# REACTION-CIRCUIT-CONTROL.net
KiCad netlist of a schematic drawn in Altium Designer
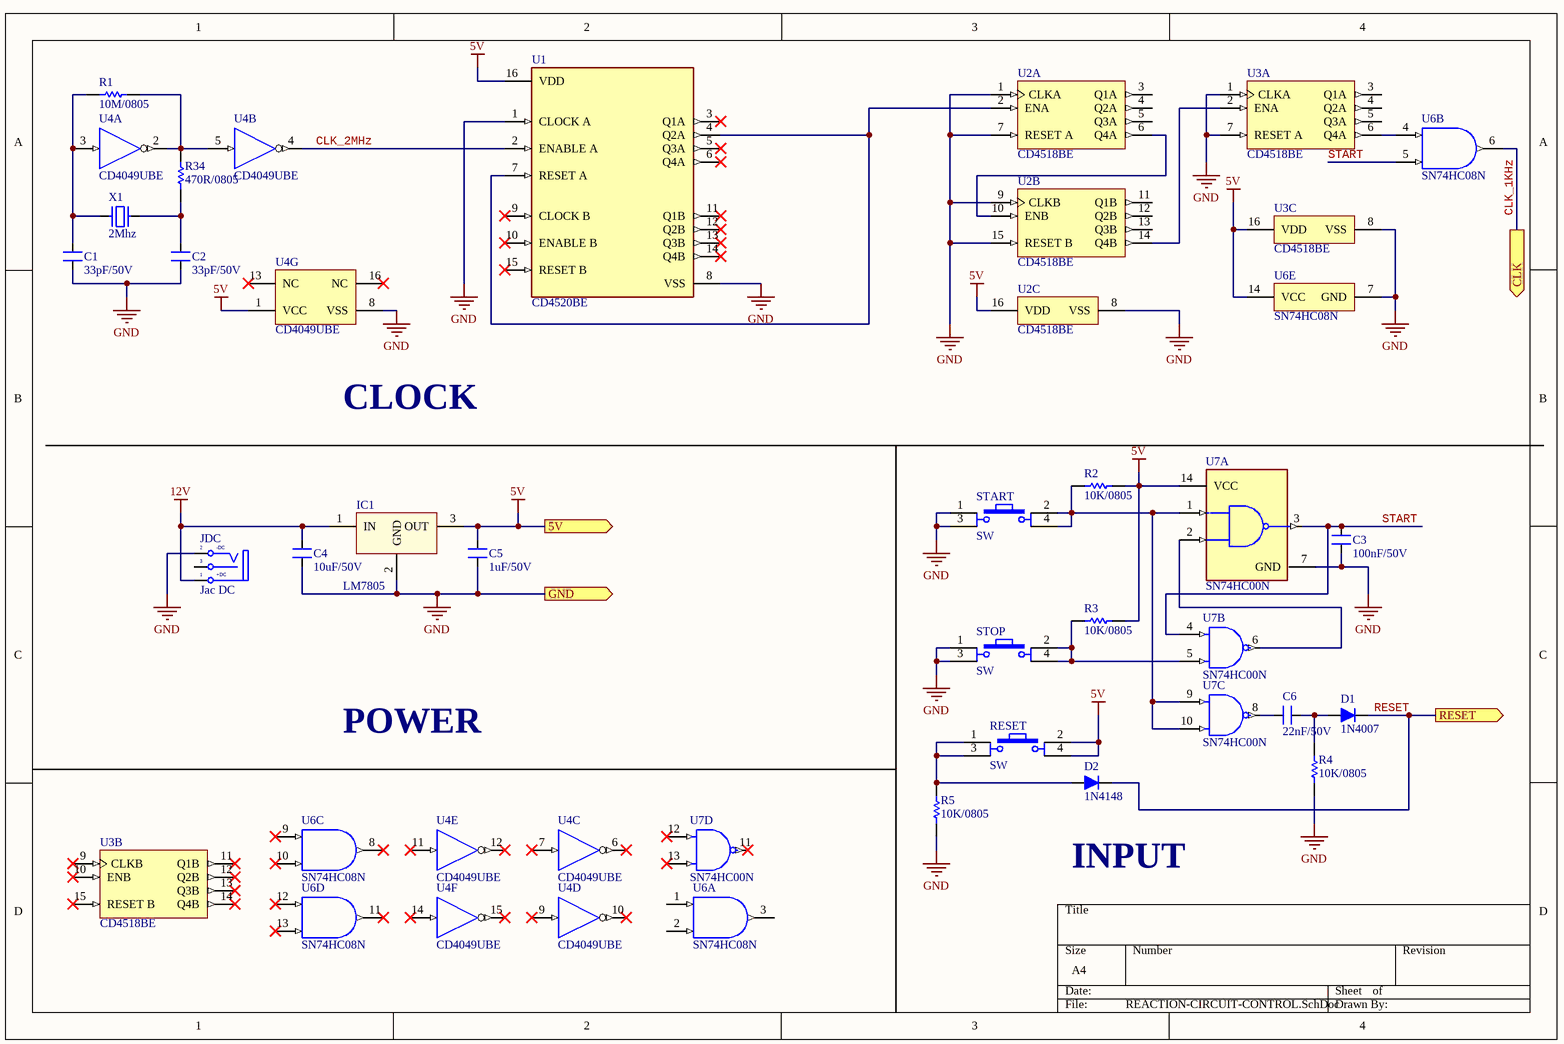
[diagram p0: REACTION-CIRCUIT-CONTROL.SchDoc]

(export (version "E")
  (design (tool "Eeschema 10.0.6"))
  (components
    (comp (ref "C1")
      (value "33pF/50V")
      (footprint "Cap 0805(2012)")
      (description "Ceramic Capacitor 1nF/50V (+-20% TH)/(+10%SMD)")
      (libsource (lib "Duc") (part "CAP_CER_1nF_50V_NPOL"))
    )
    (comp (ref "C2")
      (value "33pF/50V")
      (footprint "Cap 0805(2012)")
      (description "Ceramic Capacitor 1nF/50V (+-20% TH)/(+10%SMD)")
      (libsource (lib "Duc") (part "CAP_CER_1nF_50V_NPOL"))
    )
    (comp (ref "C3")
      (value "100nF/50V")
      (footprint "Cap 0805(2012)")
      (description "Ceramic Capacitor 1nF/50V (+-20% TH)/(+10%SMD)")
      (libsource (lib "Duc") (part "CAP_CER_1nF_50V_NPOL"))
    )
    (comp (ref "C4")
      (value "10uF/50V")
      (footprint "Cap 0805(2012)")
      (description "Ceramic Capacitor 1nF/50V (+-20% TH)/(+10%SMD)")
      (libsource (lib "Duc") (part "CAP_CER_1nF_50V_NPOL"))
    )
    (comp (ref "C5")
      (value "1uF/50V")
      (footprint "Cap 0805(2012)")
      (description "Ceramic Capacitor 1nF/50V (+-20% TH)/(+10%SMD)")
      (libsource (lib "Duc") (part "CAP_CER_1nF_50V_NPOL"))
    )
    (comp (ref "C6")
      (value "22nF/50V")
      (footprint "Cap 0805(2012)")
      (description "Ceramic Capacitor 1nF/50V (+-20% TH)/(+10%SMD)")
      (libsource (lib "Duc") (part "CAP_CER_1nF_50V_NPOL"))
    )
    (comp (ref "D1")
      (value "1N4007")
      (footprint "1N4007")
      (description "Diode LS 1A 1000V DO-41")
      (libsource (lib "Duc") (part "1N4007"))
    )
    (comp (ref "D2")
      (value "1N4148")
      (footprint "1N4007")
      (description "Diode LS 1A 1000V DO-41")
      (libsource (lib "Duc") (part "1N4007"))
    )
    (comp (ref "IC1")
      (value "LM7805")
      (footprint "QTO-220H3")
      (description "On ap +, from + 5 to + 24VDC")
      (libsource (lib "MinhHa_Integrated_Library") (part "LM78xx"))
    )
    (comp (ref "JDC")
      (value "Jac DC")
      (footprint "DC-IN")
      (description "Jac DC input")
      (libsource (lib "MinhHa_Integrated_Library") (part "DCIN"))
    )
    (comp (ref "R1")
      (value "10M/0805")
      (footprint "Res 0805(2012)")
      (description "Resistor 0805")
      (libsource (lib "Duc") (part "Resistor 0805"))
    )
    (comp (ref "R2")
      (value "10K/0805")
      (footprint "Res 0805(2012)")
      (description "Resistor 0805")
      (libsource (lib "Duc") (part "Resistor 0805"))
    )
    (comp (ref "R3")
      (value "10K/0805")
      (footprint "Res 0805(2012)")
      (description "Resistor 0805")
      (libsource (lib "Duc") (part "Resistor 0805"))
    )
    (comp (ref "R4")
      (value "10K/0805")
      (footprint "Res 0805(2012)")
      (description "Resistor 0805")
      (libsource (lib "Duc") (part "Resistor 0805"))
    )
    (comp (ref "R5")
      (value "10K/0805")
      (footprint "Res 0805(2012)")
      (description "Resistor 0805")
      (libsource (lib "Duc") (part "Resistor 0805"))
    )
    (comp (ref "R34")
      (value "470R/0805")
      (footprint "Res 0805(2012)")
      (description "Resistor 0805")
      (libsource (lib "Duc") (part "Resistor 0805"))
    )
    (comp (ref "RESET")
      (value "SW")
      (footprint "SW4B")
      (description "Switch button 4 pin")
      (libsource (lib "MinhHa_Integrated_Library") (part "SW4"))
    )
    (comp (ref "START")
      (value "SW")
      (footprint "SW4B")
      (description "Switch button 4 pin")
      (libsource (lib "MinhHa_Integrated_Library") (part "SW4"))
    )
    (comp (ref "STOP")
      (value "SW")
      (footprint "SW4B")
      (description "Switch button 4 pin")
      (libsource (lib "MinhHa_Integrated_Library") (part "SW4"))
    )
    (comp (ref "U1")
      (value "CD4520BE")
      (footprint "FP-N0016A-MFG")
      (description "IC DUAL BINARY UP COUNTER 16-DIP")
      (libsource (lib "Altium Content Vault") (part "bdd40e6c57bfb003857edd1337e34ab"))
    )
    (comp (ref "U2")
      (value "CD4518BE")
      (footprint "N0016A")
      (description "CMOS Dual BCD Up-Counter, N0016A, TUBE")
      (fields
        (field (name "MANUFACTURER") "Texas Instruments")
        (field (name "GENERIC PART NUMBER") "CD4518B")
      )
      (libsource (lib "Altium Content Vault") (part "TI-CD45XXB-16"))
    )
    (comp (ref "U3")
      (value "CD4518BE")
      (footprint "N0016A")
      (description "CMOS Dual BCD Up-Counter, N0016A, TUBE")
      (fields
        (field (name "MANUFACTURER") "Texas Instruments")
        (field (name "GENERIC PART NUMBER") "CD4518B")
      )
      (libsource (lib "Altium Content Vault") (part "TI-CD45XXB-16"))
    )
    (comp (ref "U4")
      (value "CD4049UBE")
      (footprint "N0016A")
      (description "CMOS Hex Inverting Buffer/Converter, N0016A, TUBE")
      (fields
        (field (name "GENERIC PART NUMBER") "CD4049UB")
        (field (name "MANUFACTURER") "Texas Instruments")
      )
      (libsource (lib "Altium Content Vault") (part "TI-CD4049UB-16"))
    )
    (comp (ref "U6")
      (value "SN74HC08N")
      (footprint "N0014A")
      (description "Quadruple 2-Input Positive-AND Gates, N0014A, TUBE")
      (fields
        (field (name "GENERIC PART NUMBER") "SN74HC08")
        (field (name "MANUFACTURER") "Texas Instruments")
      )
      (libsource (lib "Altium Content Vault") (part "TI-AND-4-2IN-14"))
    )
    (comp (ref "U7")
      (value "SN74HC00N")
      (footprint "FP-N0014A-MFG")
      (description "IC GATE NAND 4CH 2-INP 14DIP")
      (libsource (lib "Altium Content Vault") (part "0b9c136352749c62e1c326cbc0064d4"))
    )
    (comp (ref "X1")
      (value "2Mhz")
      (footprint "XT2")
      (description "Crystal, 32.768 KHz, -40 to 85 degC, 3.2 x 1.5 x 0.9 mm SMD")
      (libsource (lib "LIBRARY_MuaLinhKien") (part "XT2"))
    )
  )
  (nets
    (net (code "1") (name "/CLK_1KHz") (class "Default")
      (node (ref "U6") (pin "6") (pinfunction "2Y_6") (pintype "output"))
    )
    (net (code "2") (name "/CLK_2MHz") (class "Default")
      (node (ref "U1") (pin "2") (pinfunction "ENABLE_A_2") (pintype "input"))
      (node (ref "U4") (pin "4") (pinfunction "H=~{B}_4") (pintype "output"))
    )
    (net (code "3") (name "/RESET") (class "Default")
      (node (ref "D1") (pin "2") (pinfunction "K_2") (pintype "passive"))
      (node (ref "D2") (pin "2") (pinfunction "K_2") (pintype "passive"))
    )
    (net (code "4") (name "/START") (class "Default")
      (node (ref "C3") (pin "2") (pinfunction "2_2") (pintype "passive"))
      (node (ref "U6") (pin "5") (pinfunction "2B_5") (pintype "input"))
      (node (ref "U7") (pin "3") (pinfunction "1Y_3") (pintype "output"))
      (node (ref "U7") (pin "4") (pinfunction "2A_4") (pintype "input"))
    )
    (net (code "5") (name "5V") (class "Default")
      (node (ref "C5") (pin "2") (pinfunction "2_2") (pintype "passive"))
      (node (ref "IC1") (pin "3") (pinfunction "OUT_3") (pintype "passive"))
      (node (ref "R2") (pin "2") (pinfunction "2_2") (pintype "passive"))
      (node (ref "R3") (pin "2") (pinfunction "2_2") (pintype "passive"))
      (node (ref "RESET") (pin "2") (pintype "passive"))
      (node (ref "RESET") (pin "4") (pintype "passive"))
      (node (ref "U1") (pin "16") (pinfunction "VDD_16") (pintype "power_in"))
      (node (ref "U2") (pin "16") (pinfunction "VDD_16") (pintype "power_in"))
      (node (ref "U3") (pin "16") (pinfunction "VDD_16") (pintype "power_in"))
      (node (ref "U4") (pin "1") (pinfunction "VCC_1") (pintype "power_in"))
      (node (ref "U6") (pin "14") (pinfunction "VCC_14") (pintype "power_in"))
      (node (ref "U7") (pin "14") (pinfunction "VCC_14") (pintype "power_in"))
    )
    (net (code "6") (name "12V") (class "Default")
      (node (ref "C4") (pin "2") (pinfunction "2_2") (pintype "passive"))
      (node (ref "IC1") (pin "1") (pinfunction "IN_1") (pintype "passive"))
      (node (ref "JDC") (pin "1") (pinfunction "T_1") (pintype "passive"))
    )
    (net (code "7") (name "GND") (class "Default")
      (node (ref "C1") (pin "1") (pinfunction "1_1") (pintype "passive"))
      (node (ref "C2") (pin "1") (pinfunction "1_1") (pintype "passive"))
      (node (ref "C3") (pin "1") (pinfunction "1_1") (pintype "passive"))
      (node (ref "C4") (pin "1") (pinfunction "1_1") (pintype "passive"))
      (node (ref "C5") (pin "1") (pinfunction "1_1") (pintype "passive"))
      (node (ref "IC1") (pin "2") (pinfunction "GND_2") (pintype "passive"))
      (node (ref "JDC") (pin "2") (pinfunction "TN_2") (pintype "passive"))
      (node (ref "R4") (pin "2") (pinfunction "2_2") (pintype "passive"))
      (node (ref "R5") (pin "2") (pinfunction "2_2") (pintype "passive"))
      (node (ref "START") (pin "1") (pintype "passive"))
      (node (ref "START") (pin "3") (pintype "passive"))
      (node (ref "STOP") (pin "1") (pintype "passive"))
      (node (ref "STOP") (pin "3") (pintype "passive"))
      (node (ref "U1") (pin "1") (pinfunction "CLOCK_A_1") (pintype "input"))
      (node (ref "U1") (pin "8") (pinfunction "VSS_8") (pintype "power_in"))
      (node (ref "U2") (pin "1") (pinfunction "CLKA_1") (pintype "input"))
      (node (ref "U2") (pin "15") (pinfunction "RESET_B_15") (pintype "input"))
      (node (ref "U2") (pin "7") (pinfunction "RESET_A_7") (pintype "input"))
      (node (ref "U2") (pin "8") (pinfunction "VSS_8") (pintype "power_in"))
      (node (ref "U2") (pin "9") (pinfunction "CLKB_9") (pintype "input"))
      (node (ref "U3") (pin "1") (pinfunction "CLKA_1") (pintype "input"))
      (node (ref "U3") (pin "7") (pinfunction "RESET_A_7") (pintype "input"))
      (node (ref "U3") (pin "8") (pinfunction "VSS_8") (pintype "power_in"))
      (node (ref "U4") (pin "8") (pinfunction "VSS_8") (pintype "power_in"))
      (node (ref "U6") (pin "7") (pinfunction "GND_7") (pintype "power_in"))
      (node (ref "U7") (pin "7") (pinfunction "GND_7") (pintype "power_in"))
    )
    (net (code "8") (name "Net-(C2-Pad2)") (class "Default")
      (node (ref "C2") (pin "2") (pinfunction "2_2") (pintype "passive"))
      (node (ref "R34") (pin "2") (pinfunction "2_2") (pintype "passive"))
      (node (ref "X1") (pin "2") (pinfunction "2_2") (pintype "passive"))
    )
    (net (code "9") (name "Net-(D1-A)") (class "Default")
      (node (ref "C6") (pin "1") (pinfunction "1_1") (pintype "passive"))
      (node (ref "D1") (pin "1") (pinfunction "A_1") (pintype "passive"))
      (node (ref "R4") (pin "1") (pinfunction "1_1") (pintype "passive"))
    )
    (net (code "10") (name "Net-(D2-A)") (class "Default")
      (node (ref "D2") (pin "1") (pinfunction "A_1") (pintype "passive"))
      (node (ref "R5") (pin "1") (pinfunction "1_1") (pintype "passive"))
      (node (ref "RESET") (pin "1") (pintype "passive"))
      (node (ref "RESET") (pin "3") (pintype "passive"))
    )
    (net (code "11") (name "Net-(U1-Q2A)") (class "Default")
      (node (ref "U1") (pin "4") (pinfunction "Q2A_4") (pintype "output"))
      (node (ref "U1") (pin "7") (pinfunction "RESET_A_7") (pintype "input"))
      (node (ref "U2") (pin "2") (pinfunction "ENA_2") (pintype "input"))
    )
    (net (code "12") (name "Net-(U2A-Q4A)") (class "Default")
      (node (ref "U2") (pin "10") (pinfunction "ENB_10") (pintype "input"))
      (node (ref "U2") (pin "6") (pinfunction "Q4A_6") (pintype "output"))
    )
    (net (code "13") (name "Net-(U2B-Q4B)") (class "Default")
      (node (ref "U2") (pin "14") (pinfunction "Q4B_14") (pintype "output"))
      (node (ref "U3") (pin "2") (pinfunction "ENA_2") (pintype "input"))
    )
    (net (code "14") (name "Net-(U3A-Q4A)") (class "Default")
      (node (ref "U3") (pin "6") (pinfunction "Q4A_6") (pintype "output"))
      (node (ref "U6") (pin "4") (pinfunction "2A_4") (pintype "input"))
    )
    (net (code "15") (name "Net-(U4A-A)") (class "Default")
      (node (ref "C1") (pin "2") (pinfunction "2_2") (pintype "passive"))
      (node (ref "R1") (pin "2") (pinfunction "2_2") (pintype "passive"))
      (node (ref "U4") (pin "3") (pinfunction "A_3") (pintype "input"))
      (node (ref "X1") (pin "1") (pinfunction "1_1") (pintype "passive"))
    )
    (net (code "16") (name "Net-(U4A-G=~{A})") (class "Default")
      (node (ref "R1") (pin "1") (pinfunction "1_1") (pintype "passive"))
      (node (ref "R34") (pin "1") (pinfunction "1_1") (pintype "passive"))
      (node (ref "U4") (pin "2") (pinfunction "G=~{A}_2") (pintype "output"))
      (node (ref "U4") (pin "5") (pinfunction "B_5") (pintype "input"))
    )
    (net (code "17") (name "Net-(U7A-1A)") (class "Default")
      (node (ref "R2") (pin "1") (pinfunction "1_1") (pintype "passive"))
      (node (ref "START") (pin "2") (pintype "passive"))
      (node (ref "START") (pin "4") (pintype "passive"))
      (node (ref "U7") (pin "1") (pinfunction "1A_1") (pintype "input"))
      (node (ref "U7") (pin "10") (pinfunction "3B_10") (pintype "input"))
      (node (ref "U7") (pin "9") (pinfunction "3A_9") (pintype "input"))
    )
    (net (code "18") (name "Net-(U7A-1B)") (class "Default")
      (node (ref "U7") (pin "2") (pinfunction "1B_2") (pintype "input"))
      (node (ref "U7") (pin "6") (pinfunction "2Y_6") (pintype "output"))
    )
    (net (code "19") (name "Net-(U7B-2B)") (class "Default")
      (node (ref "R3") (pin "1") (pinfunction "1_1") (pintype "passive"))
      (node (ref "STOP") (pin "2") (pintype "passive"))
      (node (ref "STOP") (pin "4") (pintype "passive"))
      (node (ref "U7") (pin "5") (pinfunction "2B_5") (pintype "input"))
    )
    (net (code "20") (name "Net-(U7C-3Y)") (class "Default")
      (node (ref "C6") (pin "2") (pinfunction "2_2") (pintype "passive"))
      (node (ref "U7") (pin "8") (pinfunction "3Y_8") (pintype "output"))
    )
    (net (code "21") (name "unconnected-(JDC-S-Pad3)") (class "Default")
      (node (ref "JDC") (pin "3") (pinfunction "S_3") (pintype "power_in"))
    )
    (net (code "22") (name "unconnected-(U1-CLOCK_B-Pad9)") (class "Default")
      (node (ref "U1") (pin "9") (pinfunction "CLOCK_B_9") (pintype "input+no_connect"))
    )
    (net (code "23") (name "unconnected-(U1-ENABLE_B-Pad10)") (class "Default")
      (node (ref "U1") (pin "10") (pinfunction "ENABLE_B_10") (pintype "input+no_connect"))
    )
    (net (code "24") (name "unconnected-(U1-Q1A-Pad3)") (class "Default")
      (node (ref "U1") (pin "3") (pinfunction "Q1A_3") (pintype "output+no_connect"))
    )
    (net (code "25") (name "unconnected-(U1-Q1B-Pad11)") (class "Default")
      (node (ref "U1") (pin "11") (pinfunction "Q1B_11") (pintype "output+no_connect"))
    )
    (net (code "26") (name "unconnected-(U1-Q2B-Pad12)") (class "Default")
      (node (ref "U1") (pin "12") (pinfunction "Q2B_12") (pintype "output+no_connect"))
    )
    (net (code "27") (name "unconnected-(U1-Q3A-Pad5)") (class "Default")
      (node (ref "U1") (pin "5") (pinfunction "Q3A_5") (pintype "output+no_connect"))
    )
    (net (code "28") (name "unconnected-(U1-Q3B-Pad13)") (class "Default")
      (node (ref "U1") (pin "13") (pinfunction "Q3B_13") (pintype "output+no_connect"))
    )
    (net (code "29") (name "unconnected-(U1-Q4A-Pad6)") (class "Default")
      (node (ref "U1") (pin "6") (pinfunction "Q4A_6") (pintype "output+no_connect"))
    )
    (net (code "30") (name "unconnected-(U1-Q4B-Pad14)") (class "Default")
      (node (ref "U1") (pin "14") (pinfunction "Q4B_14") (pintype "output+no_connect"))
    )
    (net (code "31") (name "unconnected-(U1-RESET_B-Pad15)") (class "Default")
      (node (ref "U1") (pin "15") (pinfunction "RESET_B_15") (pintype "input+no_connect"))
    )
    (net (code "32") (name "unconnected-(U2A-Q1A-Pad3)") (class "Default")
      (node (ref "U2") (pin "3") (pinfunction "Q1A_3") (pintype "output"))
    )
    (net (code "33") (name "unconnected-(U2A-Q2A-Pad4)") (class "Default")
      (node (ref "U2") (pin "4") (pinfunction "Q2A_4") (pintype "output"))
    )
    (net (code "34") (name "unconnected-(U2A-Q3A-Pad5)") (class "Default")
      (node (ref "U2") (pin "5") (pinfunction "Q3A_5") (pintype "output"))
    )
    (net (code "35") (name "unconnected-(U2B-Q1B-Pad11)") (class "Default")
      (node (ref "U2") (pin "11") (pinfunction "Q1B_11") (pintype "output"))
    )
    (net (code "36") (name "unconnected-(U2B-Q2B-Pad12)") (class "Default")
      (node (ref "U2") (pin "12") (pinfunction "Q2B_12") (pintype "output"))
    )
    (net (code "37") (name "unconnected-(U2B-Q3B-Pad13)") (class "Default")
      (node (ref "U2") (pin "13") (pinfunction "Q3B_13") (pintype "output"))
    )
    (net (code "38") (name "unconnected-(U3A-Q1A-Pad3)") (class "Default")
      (node (ref "U3") (pin "3") (pinfunction "Q1A_3") (pintype "output"))
    )
    (net (code "39") (name "unconnected-(U3A-Q2A-Pad4)") (class "Default")
      (node (ref "U3") (pin "4") (pinfunction "Q2A_4") (pintype "output"))
    )
    (net (code "40") (name "unconnected-(U3A-Q3A-Pad5)") (class "Default")
      (node (ref "U3") (pin "5") (pinfunction "Q3A_5") (pintype "output"))
    )
    (net (code "41") (name "unconnected-(U3B-CLKB-Pad9)") (class "Default")
      (node (ref "U3") (pin "9") (pinfunction "CLKB_9") (pintype "input+no_connect"))
    )
    (net (code "42") (name "unconnected-(U3B-ENB-Pad10)") (class "Default")
      (node (ref "U3") (pin "10") (pinfunction "ENB_10") (pintype "input+no_connect"))
    )
    (net (code "43") (name "unconnected-(U3B-Q1B-Pad11)") (class "Default")
      (node (ref "U3") (pin "11") (pinfunction "Q1B_11") (pintype "output+no_connect"))
    )
    (net (code "44") (name "unconnected-(U3B-Q2B-Pad12)") (class "Default")
      (node (ref "U3") (pin "12") (pinfunction "Q2B_12") (pintype "output+no_connect"))
    )
    (net (code "45") (name "unconnected-(U3B-Q3B-Pad13)") (class "Default")
      (node (ref "U3") (pin "13") (pinfunction "Q3B_13") (pintype "output+no_connect"))
    )
    (net (code "46") (name "unconnected-(U3B-Q4B-Pad14)") (class "Default")
      (node (ref "U3") (pin "14") (pinfunction "Q4B_14") (pintype "output+no_connect"))
    )
    (net (code "47") (name "unconnected-(U3B-RESET_B-Pad15)") (class "Default")
      (node (ref "U3") (pin "15") (pinfunction "RESET_B_15") (pintype "input+no_connect"))
    )
    (net (code "48") (name "unconnected-(U4C-C-Pad7)") (class "Default")
      (node (ref "U4") (pin "7") (pinfunction "C_7") (pintype "input+no_connect"))
    )
    (net (code "49") (name "unconnected-(U4C-I=~{C}-Pad6)") (class "Default")
      (node (ref "U4") (pin "6") (pinfunction "I=~{C}_6") (pintype "output+no_connect"))
    )
    (net (code "50") (name "unconnected-(U4D-D-Pad9)") (class "Default")
      (node (ref "U4") (pin "9") (pinfunction "D_9") (pintype "input+no_connect"))
    )
    (net (code "51") (name "unconnected-(U4D-J=~{D}-Pad10)") (class "Default")
      (node (ref "U4") (pin "10") (pinfunction "J=~{D}_10") (pintype "output+no_connect"))
    )
    (net (code "52") (name "unconnected-(U4E-E-Pad11)") (class "Default")
      (node (ref "U4") (pin "11") (pinfunction "E_11") (pintype "input+no_connect"))
    )
    (net (code "53") (name "unconnected-(U4E-K=~{E}-Pad12)") (class "Default")
      (node (ref "U4") (pin "12") (pinfunction "K=~{E}_12") (pintype "output+no_connect"))
    )
    (net (code "54") (name "unconnected-(U4F-F-Pad14)") (class "Default")
      (node (ref "U4") (pin "14") (pinfunction "F_14") (pintype "input+no_connect"))
    )
    (net (code "55") (name "unconnected-(U4F-L=~{F}-Pad15)") (class "Default")
      (node (ref "U4") (pin "15") (pinfunction "L=~{F}_15") (pintype "output+no_connect"))
    )
    (net (code "56") (name "unconnected-(U4G-NC-Pad13)") (class "Default")
      (node (ref "U4") (pin "13") (pinfunction "NC_13") (pintype "passive+no_connect"))
    )
    (net (code "57") (name "unconnected-(U4G-NC-Pad16)") (class "Default")
      (node (ref "U4") (pin "16") (pinfunction "NC_16") (pintype "passive+no_connect"))
    )
    (net (code "58") (name "unconnected-(U6A-1A-Pad1)") (class "Default")
      (node (ref "U6") (pin "1") (pinfunction "1A_1") (pintype "input"))
    )
    (net (code "59") (name "unconnected-(U6A-1B-Pad2)") (class "Default")
      (node (ref "U6") (pin "2") (pinfunction "1B_2") (pintype "input"))
    )
    (net (code "60") (name "unconnected-(U6A-1Y-Pad3)") (class "Default")
      (node (ref "U6") (pin "3") (pinfunction "1Y_3") (pintype "output"))
    )
    (net (code "61") (name "unconnected-(U6C-3A-Pad9)") (class "Default")
      (node (ref "U6") (pin "9") (pinfunction "3A_9") (pintype "input+no_connect"))
    )
    (net (code "62") (name "unconnected-(U6C-3B-Pad10)") (class "Default")
      (node (ref "U6") (pin "10") (pinfunction "3B_10") (pintype "input+no_connect"))
    )
    (net (code "63") (name "unconnected-(U6C-3Y-Pad8)") (class "Default")
      (node (ref "U6") (pin "8") (pinfunction "3Y_8") (pintype "output+no_connect"))
    )
    (net (code "64") (name "unconnected-(U6D-4A-Pad12)") (class "Default")
      (node (ref "U6") (pin "12") (pinfunction "4A_12") (pintype "input+no_connect"))
    )
    (net (code "65") (name "unconnected-(U6D-4B-Pad13)") (class "Default")
      (node (ref "U6") (pin "13") (pinfunction "4B_13") (pintype "input+no_connect"))
    )
    (net (code "66") (name "unconnected-(U6D-4Y-Pad11)") (class "Default")
      (node (ref "U6") (pin "11") (pinfunction "4Y_11") (pintype "output+no_connect"))
    )
    (net (code "67") (name "unconnected-(U7D-4A-Pad12)") (class "Default")
      (node (ref "U7") (pin "12") (pinfunction "4A_12") (pintype "input+no_connect"))
    )
    (net (code "68") (name "unconnected-(U7D-4B-Pad13)") (class "Default")
      (node (ref "U7") (pin "13") (pinfunction "4B_13") (pintype "input+no_connect"))
    )
    (net (code "69") (name "unconnected-(U7D-4Y-Pad11)") (class "Default")
      (node (ref "U7") (pin "11") (pinfunction "4Y_11") (pintype "output+no_connect"))
    )
  )
)
